# I2C_Puppet.net
KiCad netlist of a schematic drawn in EAGLE
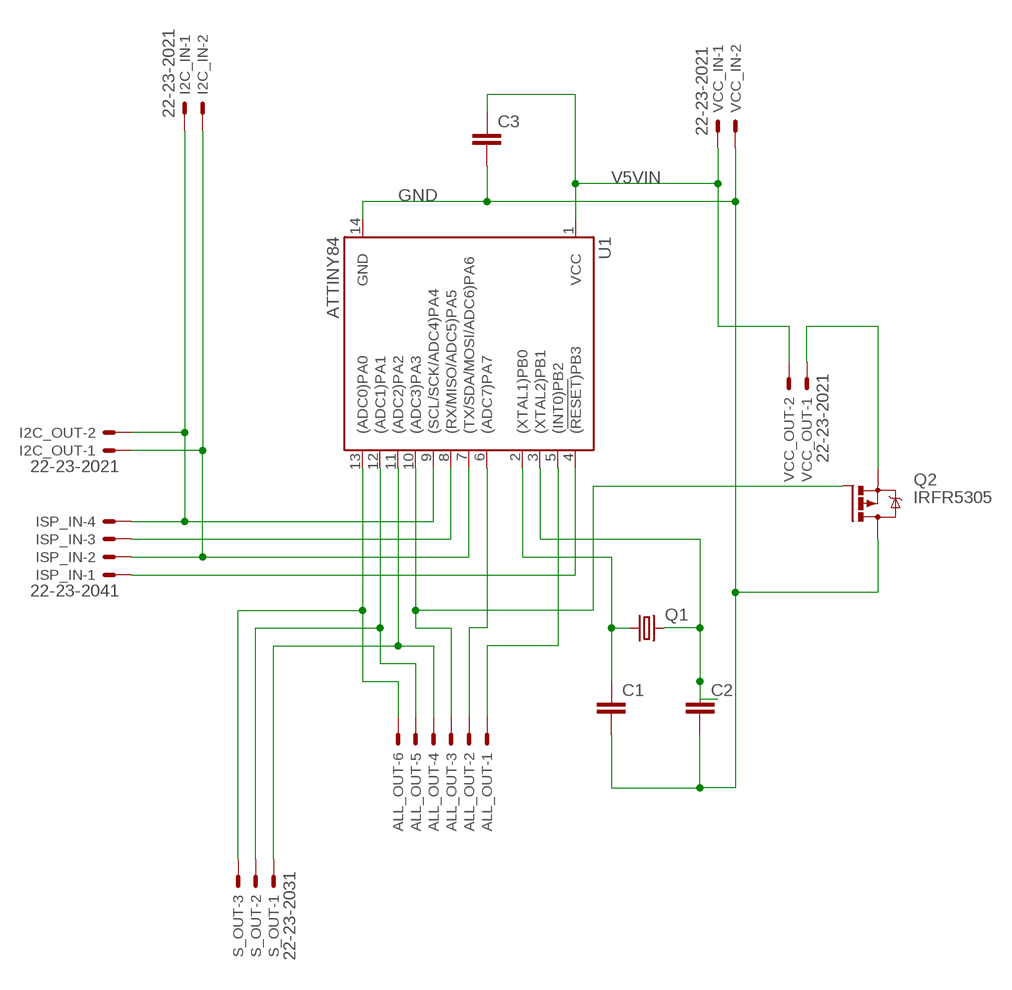
[diagram p0: schematic, sheet 1]

(export (version "E")
  (design (tool "Eeschema 10.0.6"))
  (components
    (comp (ref "ALL_OUT")
      (value "22-23-2061")
      (footprint "eagle-import:22-23-2061")
      (fields (field (name "MF") "MOLEX"))
      (libsource (lib "eagle-import") (part "22-23-2061"))
    )
    (comp (ref "C1")
      (value "C-EUC1210")
      (footprint "eagle-import:C1210")
      (libsource (lib "eagle-import") (part "C-EUC1210"))
    )
    (comp (ref "C2")
      (value "C-EUC1210")
      (footprint "eagle-import:C1210")
      (libsource (lib "eagle-import") (part "C-EUC1210"))
    )
    (comp (ref "C3")
      (value "C-EUC1210")
      (footprint "eagle-import:C1210")
      (libsource (lib "eagle-import") (part "C-EUC1210"))
    )
    (comp (ref "I2C_IN")
      (value "22-23-2021")
      (footprint "eagle-import:22-23-2021")
      (fields (field (name "MF") "MOLEX"))
      (libsource (lib "eagle-import") (part "22-23-2021"))
    )
    (comp (ref "I2C_OUT")
      (value "22-23-2021")
      (footprint "eagle-import:22-23-2021")
      (fields (field (name "MF") "MOLEX"))
      (libsource (lib "eagle-import") (part "22-23-2021"))
    )
    (comp (ref "ISP_IN")
      (value "22-23-2041")
      (footprint "eagle-import:22-23-2041")
      (fields (field (name "MF") "MOLEX"))
      (libsource (lib "eagle-import") (part "22-23-2041"))
    )
    (comp (ref "Q1")
      (value "CRYSTALHC49UP")
      (footprint "eagle-import:HC49UP")
      (libsource (lib "eagle-import") (part "CRYSTALHC49UP"))
    )
    (comp (ref "Q2")
      (value "IRFR5305")
      (footprint "eagle-import:D-PAK_TO252AA")
      (libsource (lib "eagle-import") (part "IRF?5305R"))
    )
    (comp (ref "S_OUT")
      (value "22-23-2031")
      (footprint "eagle-import:22-23-2031")
      (fields (field (name "MF") "MOLEX"))
      (libsource (lib "eagle-import") (part "22-23-2031"))
    )
    (comp (ref "U1")
      (value "ATTINY84")
      (footprint "eagle-import:SO14")
      (libsource (lib "eagle-import") (part "ATTINY84"))
    )
    (comp (ref "VCC_IN")
      (value "22-23-2021")
      (footprint "eagle-import:22-23-2021")
      (fields (field (name "MF") "MOLEX"))
      (libsource (lib "eagle-import") (part "22-23-2021"))
    )
    (comp (ref "VCC_OUT")
      (value "22-23-2021")
      (footprint "eagle-import:22-23-2021")
      (fields (field (name "MF") "MOLEX"))
      (libsource (lib "eagle-import") (part "22-23-2021"))
    )
  )
  (nets
    (net (code "1") (name "/GND") (class "Default")
      (node (ref "C1") (pin "2") (pinfunction "2_2") (pintype "passive"))
      (node (ref "C2") (pin "2") (pinfunction "2_2") (pintype "passive"))
      (node (ref "C3") (pin "2") (pinfunction "2_2") (pintype "passive"))
      (node (ref "Q2") (pin "4") (pinfunction "D_4") (pintype "passive"))
      (node (ref "U1") (pin "14") (pinfunction "GND_14") (pintype "bidirectional"))
      (node (ref "VCC_IN") (pin "2") (pinfunction "S_2") (pintype "passive"))
    )
    (net (code "2") (name "/V5VIN") (class "Default")
      (node (ref "C3") (pin "1") (pinfunction "1_1") (pintype "passive"))
      (node (ref "U1") (pin "1") (pinfunction "VCC_1") (pintype "bidirectional"))
      (node (ref "VCC_IN") (pin "1") (pinfunction "S_1") (pintype "passive"))
      (node (ref "VCC_OUT") (pin "2") (pinfunction "S_2") (pintype "passive"))
    )
    (net (code "3") (name "Net-(ALL_OUTA-S)") (class "Default")
      (node (ref "ALL_OUT") (pin "1") (pinfunction "S_1") (pintype "passive"))
      (node (ref "U1") (pin "5") (pinfunction "(INT0)PB2_5") (pintype "bidirectional"))
    )
    (net (code "4") (name "Net-(ALL_OUTB-S)") (class "Default")
      (node (ref "ALL_OUT") (pin "2") (pinfunction "S_2") (pintype "passive"))
      (node (ref "U1") (pin "6") (pinfunction "(ADC7)PA7_6") (pintype "bidirectional"))
    )
    (net (code "5") (name "Net-(ALL_OUTC-S)") (class "Default")
      (node (ref "ALL_OUT") (pin "3") (pinfunction "S_3") (pintype "passive"))
      (node (ref "Q2") (pin "1") (pinfunction "G_1") (pintype "passive"))
      (node (ref "U1") (pin "10") (pinfunction "(ADC3)PA3_10") (pintype "bidirectional"))
    )
    (net (code "6") (name "Net-(ALL_OUTD-S)") (class "Default")
      (node (ref "ALL_OUT") (pin "4") (pinfunction "S_4") (pintype "passive"))
      (node (ref "S_OUT") (pin "1") (pinfunction "S_1") (pintype "passive"))
      (node (ref "U1") (pin "11") (pinfunction "(ADC2)PA2_11") (pintype "bidirectional"))
    )
    (net (code "7") (name "Net-(ALL_OUTE-S)") (class "Default")
      (node (ref "ALL_OUT") (pin "5") (pinfunction "S_5") (pintype "passive"))
      (node (ref "S_OUT") (pin "2") (pinfunction "S_2") (pintype "passive"))
      (node (ref "U1") (pin "12") (pinfunction "(ADC1)PA1_12") (pintype "bidirectional"))
    )
    (net (code "8") (name "Net-(ALL_OUTF-S)") (class "Default")
      (node (ref "ALL_OUT") (pin "6") (pinfunction "S_6") (pintype "passive"))
      (node (ref "S_OUT") (pin "3") (pinfunction "S_3") (pintype "passive"))
      (node (ref "U1") (pin "13") (pinfunction "(ADC0)PA0_13") (pintype "bidirectional"))
    )
    (net (code "9") (name "Net-(I2C_INA-S)") (class "Default")
      (node (ref "I2C_IN") (pin "1") (pinfunction "S_1") (pintype "passive"))
      (node (ref "I2C_OUT") (pin "2") (pinfunction "S_2") (pintype "passive"))
      (node (ref "ISP_IN") (pin "4") (pinfunction "S_4") (pintype "passive"))
      (node (ref "U1") (pin "9") (pinfunction "(SCL/SCK/ADC4)PA4_9") (pintype "bidirectional"))
    )
    (net (code "10") (name "Net-(I2C_INB-S)") (class "Default")
      (node (ref "I2C_IN") (pin "2") (pinfunction "S_2") (pintype "passive"))
      (node (ref "I2C_OUT") (pin "1") (pinfunction "S_1") (pintype "passive"))
      (node (ref "ISP_IN") (pin "2") (pinfunction "S_2") (pintype "passive"))
      (node (ref "U1") (pin "7") (pinfunction "(TX/SDA/MOSI/ADC6)PA6_7") (pintype "bidirectional"))
    )
    (net (code "11") (name "Net-(ISP_INA-S)") (class "Default")
      (node (ref "ISP_IN") (pin "1") (pinfunction "S_1") (pintype "passive"))
      (node (ref "U1") (pin "4") (pinfunction "(~{RESET})PB3_4") (pintype "bidirectional"))
    )
    (net (code "12") (name "Net-(ISP_INC-S)") (class "Default")
      (node (ref "ISP_IN") (pin "3") (pinfunction "S_3") (pintype "passive"))
      (node (ref "U1") (pin "8") (pinfunction "(RX/MISO/ADC5)PA5_8") (pintype "bidirectional"))
    )
    (net (code "13") (name "Net-(Q2-S)") (class "Default")
      (node (ref "Q2") (pin "3") (pinfunction "S_3") (pintype "passive"))
      (node (ref "VCC_OUT") (pin "1") (pinfunction "S_1") (pintype "passive"))
    )
    (net (code "14") (name "Net-(U1-(XTAL1)PB0)") (class "Default")
      (node (ref "C1") (pin "1") (pinfunction "1_1") (pintype "passive"))
      (node (ref "Q1") (pin "1") (pinfunction "1_1") (pintype "passive"))
      (node (ref "U1") (pin "2") (pinfunction "(XTAL1)PB0_2") (pintype "bidirectional"))
    )
    (net (code "15") (name "Net-(U1-(XTAL2)PB1)") (class "Default")
      (node (ref "C2") (pin "1") (pinfunction "1_1") (pintype "passive"))
      (node (ref "Q1") (pin "2") (pinfunction "2_2") (pintype "passive"))
      (node (ref "U1") (pin "3") (pinfunction "(XTAL2)PB1_3") (pintype "bidirectional"))
    )
  )
)
